# CAN_Expansion_V1.net
KiCad netlist of a schematic drawn in Altium Designer
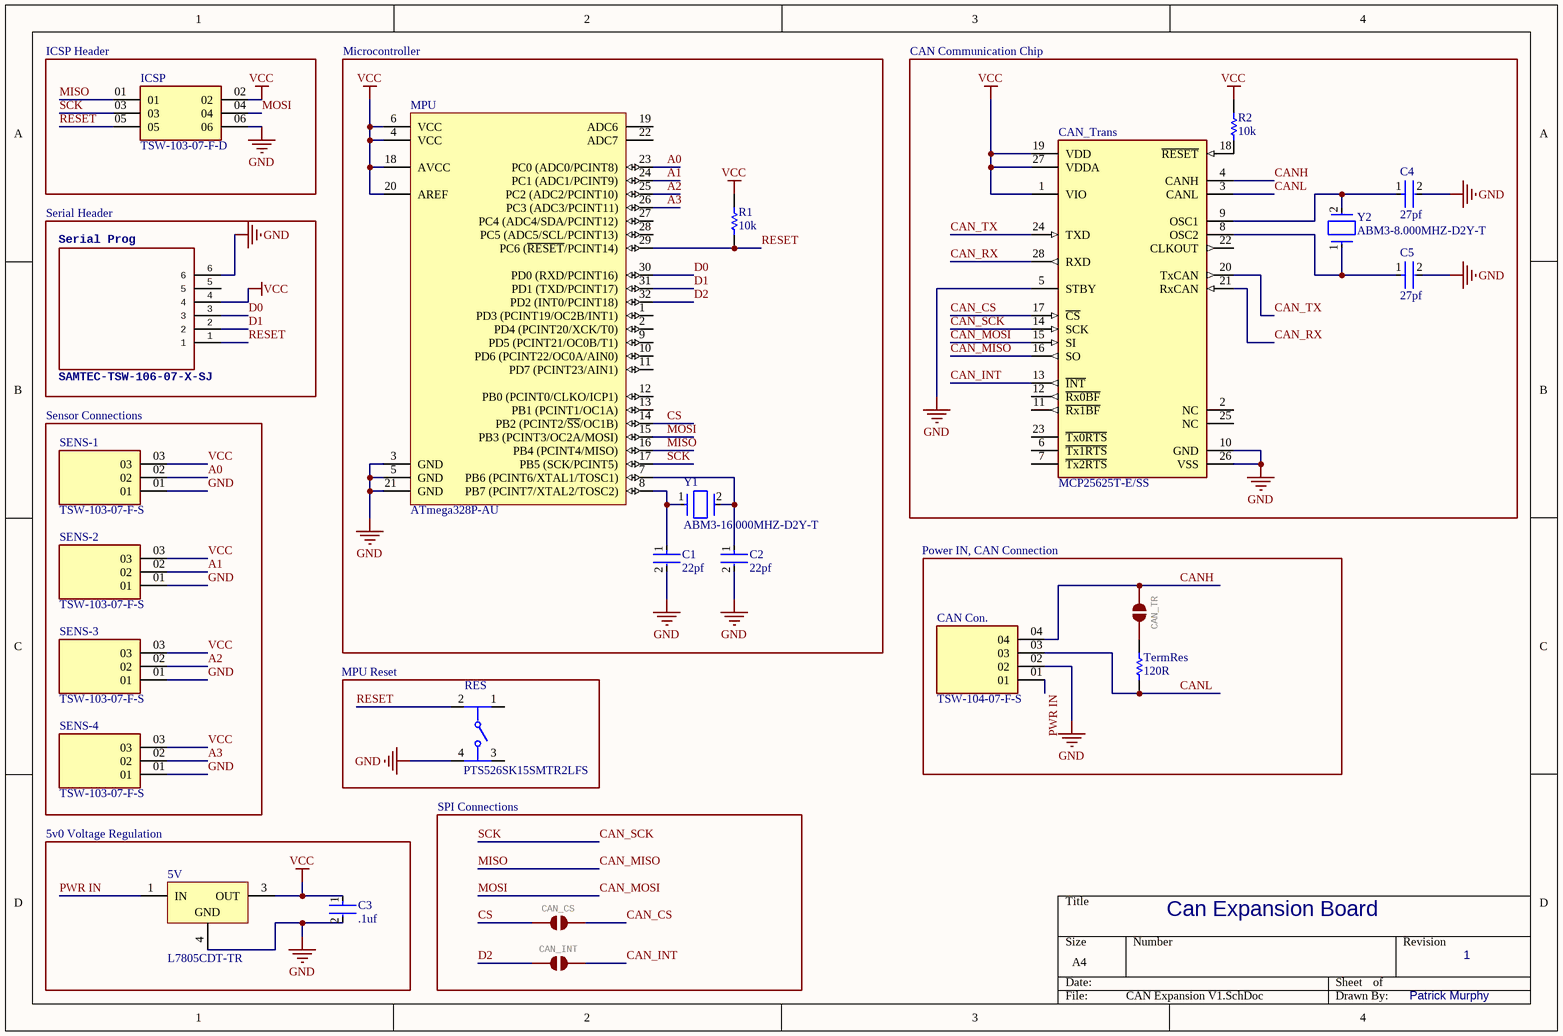
[diagram p0: CAN Expansion V1.SchDoc]

(export (version "E")
  (design (tool "Eeschema 10.0.6"))
  (components
    (comp (ref "5V")
      (value "L7805CDT-TR")
      (footprint "TO-252_N")
      (description "Positive Voltage Regulator, 3-Pin DPAK, Tape and Reel")
      (libsource (lib "Altium Content Vault") (part "PM-REG-L4940-SOT3"))
    )
    (comp (ref "C1")
      (value "22pf")
      (footprint "FP-GRM21B-0_15-IPC_C")
      (description "Chip Multilayer Ceramic Capacitors for General Purpose, 0805, 10uF, X5R, 15%, 10%, 25V")
      (fields (field (name "VOLTAGE") "25V") (field (name "TOLERANCE") "10%"))
      (libsource (lib "Altium Content Vault") (part "b4654b650e69147ec39a6b967a45e02"))
    )
    (comp (ref "C2")
      (value "22pf")
      (footprint "FP-GRM21B-0_15-IPC_C")
      (description "Chip Multilayer Ceramic Capacitors for General Purpose, 0805, 10uF, X5R, 15%, 10%, 25V")
      (fields (field (name "VOLTAGE") "25V") (field (name "TOLERANCE") "10%"))
      (libsource (lib "Altium Content Vault") (part "b4654b650e69147ec39a6b967a45e02"))
    )
    (comp (ref "C3")
      (value ".1uf")
      (footprint "FP-GRM21B-0_15-IPC_C")
      (description "Chip Multilayer Ceramic Capacitors for General Purpose, 0805, 10uF, X5R, 15%, 10%, 25V")
      (fields (field (name "VOLTAGE") "25V") (field (name "TOLERANCE") "10%"))
      (libsource (lib "Altium Content Vault") (part "b4654b650e69147ec39a6b967a45e02"))
    )
    (comp (ref "C4")
      (value "27pf")
      (footprint "FP-GRM21B-0_15-IPC_C")
      (description "Chip Multilayer Ceramic Capacitors for General Purpose, 0805, 10uF, X5R, 15%, 10%, 25V")
      (fields (field (name "VOLTAGE") "25V") (field (name "TOLERANCE") "10%"))
      (libsource (lib "Altium Content Vault") (part "b4654b650e69147ec39a6b967a45e02"))
    )
    (comp (ref "C5")
      (value "27pf")
      (footprint "FP-GRM21B-0_15-IPC_C")
      (description "Chip Multilayer Ceramic Capacitors for General Purpose, 0805, 10uF, X5R, 15%, 10%, 25V")
      (fields (field (name "VOLTAGE") "25V") (field (name "TOLERANCE") "10%"))
      (libsource (lib "Altium Content Vault") (part "b4654b650e69147ec39a6b967a45e02"))
    )
    (comp (ref "CAN Con.")
      (value "TSW-104-07-F-S")
      (footprint "SAMTEC_TSW-104-07-F-S")
      (fields (field (name "MF") "Samtec"))
      (libsource (lib "TSW-104-07-F-S") (part "TSW-104-07-F-S"))
    )
    (comp (ref "CAN_CS")
      (value "~")
      (footprint "SMT-JUMPER_2_NO_SILK")
      (libsource (lib "SparkFun-Jumpers.Library") (part "JUMPER-SMT_2_NO_SILK"))
    )
    (comp (ref "CAN_INT")
      (value "~")
      (footprint "SMT-JUMPER_2_NO_SILK")
      (libsource (lib "SparkFun-Jumpers.Library") (part "JUMPER-SMT_2_NO_SILK"))
    )
    (comp (ref "CAN_TR")
      (value "~")
      (footprint "SMT-JUMPER_2_NO_SILK")
      (libsource (lib "SparkFun-Jumpers.Library") (part "JUMPER-SMT_2_NO_SILK"))
    )
    (comp (ref "CAN_Trans")
      (value "MCP25625T-E/SS")
      (footprint "FP-C04-073-IPC_B")
      (description "IC TRANSCEIVER 1/1 28SSOP")
      (libsource (lib "Altium Content Vault") (part "1eb43db0d86e80dbea2ef2edec005e1"))
    )
    (comp (ref "ICSP")
      (value "TSW-103-07-F-D")
      (footprint "SAMTEC_TSW-103-07-F-D")
      (fields (field (name "MF") "Samtec"))
      (libsource (lib "TSW-103-07-F-D") (part "TSW-103-07-F-D"))
    )
    (comp (ref "MPU")
      (value "ATmega328P-AU")
      (footprint "32A_M")
      (libsource (lib "Altium Content Vault") (part "MC-8B-ATM48-SQ32"))
    )
    (comp (ref "R1")
      (value "10k")
      (footprint "RESC2013X60X40LL20T25")
      (fields (field (name "PART NUMBER") "ERA6AEB473V") (field (name "MANUFACTURER") "Panasonic"))
      (libsource (lib "Altium Content Vault") (part "RES"))
    )
    (comp (ref "R2")
      (value "10k")
      (footprint "RESC2013X60X40LL20T25")
      (fields (field (name "PART NUMBER") "ERA6AEB473V") (field (name "MANUFACTURER") "Panasonic"))
      (libsource (lib "Altium Content Vault") (part "RES"))
    )
    (comp (ref "RES")
      (value "PTS526SK15SMTR2LFS")
      (footprint "FP-PTS526SK15SMTR2LFS-MFG")
      (description "TACT 5.2 X 5.2, 1.5 MM H, 260GF,")
      (fields
        (field (name "MANUFACTURER") "C&K")
        (field (name "OCTOPART") "https://octopart.com/pts526+sk15+smtr2+lfs-c%26k+components-100617999")
      )
      (libsource (lib "Altium Content Vault") (part "b8895f3f4cefb76e1819d2863dba89b"))
    )
    (comp (ref "SENS-1")
      (value "TSW-103-07-F-S")
      (footprint "SAMTEC_TSW-103-07-F-S")
      (fields (field (name "MF") "Samtec"))
      (libsource (lib "TSW-103-07-F-S") (part "TSW-103-07-F-S"))
    )
    (comp (ref "SENS-2")
      (value "TSW-103-07-F-S")
      (footprint "SAMTEC_TSW-103-07-F-S")
      (fields (field (name "MF") "Samtec"))
      (libsource (lib "TSW-103-07-F-S") (part "TSW-103-07-F-S"))
    )
    (comp (ref "SENS-3")
      (value "TSW-103-07-F-S")
      (footprint "SAMTEC_TSW-103-07-F-S")
      (fields (field (name "MF") "Samtec"))
      (libsource (lib "TSW-103-07-F-S") (part "TSW-103-07-F-S"))
    )
    (comp (ref "SENS-4")
      (value "TSW-103-07-F-S")
      (footprint "SAMTEC_TSW-103-07-F-S")
      (fields (field (name "MF") "Samtec"))
      (libsource (lib "TSW-103-07-F-S") (part "TSW-103-07-F-S"))
    )
    (comp (ref "Serial Prog")
      (value "SAMTEC-TSW-106-07-X-SJ")
      (footprint "SAMTEC-TSW-106-07-X-S")
      (libsource (lib "TSW-106-07-F-S") (part "SAMTEC-TSW-106-07-X-SJ"))
    )
    (comp (ref "TermRes")
      (value "120R")
      (footprint "RESC2013X60X40LL20T25")
      (fields (field (name "PART NUMBER") "ERA6AEB473V") (field (name "MANUFACTURER") "Panasonic"))
      (libsource (lib "Altium Content Vault") (part "RES"))
    )
    (comp (ref "Y1")
      (value "ABM3-16.000MHZ-D2Y-T")
      (footprint "FP-ABM3-MFG")
      (description "Crystal 16MHz ±20ppm 18pF SMD-2 5mm x 3.2mm")
      (fields (field (name "TOLERANCE") "20ppm"))
      (libsource (lib "Altium Content Vault") (part "c23a69dc6c9e2f18f2079038eb95dd1"))
    )
    (comp (ref "Y2")
      (value "ABM3-8.000MHZ-D2Y-T")
      (footprint "FP-ABM3-MFG")
      (description "Crystal 8MHz ±20ppm 18pF SMD-2 5mm x 3.2mm")
      (fields (field (name "TOLERANCE") "20ppm"))
      (libsource (lib "Altium Content Vault") (part "c23a69dc6c9e2f18f2079038eb95dd1"))
    )
  )
  (nets
    (net (code "1") (name "/A0") (class "Default")
      (node (ref "MPU") (pin "23") (pinfunction "PC0_(ADC0/PCINT8)_23") (pintype "bidirectional"))
      (node (ref "SENS-1") (pin "02") (pinfunction "02_02") (pintype "passive"))
    )
    (net (code "2") (name "/A1") (class "Default")
      (node (ref "MPU") (pin "24") (pinfunction "PC1_(ADC1/PCINT9)_24") (pintype "bidirectional"))
      (node (ref "SENS-2") (pin "02") (pinfunction "02_02") (pintype "passive"))
    )
    (net (code "3") (name "/A2") (class "Default")
      (node (ref "MPU") (pin "25") (pinfunction "PC2_(ADC2/PCINT10)_25") (pintype "bidirectional"))
      (node (ref "SENS-3") (pin "02") (pinfunction "02_02") (pintype "passive"))
    )
    (net (code "4") (name "/A3") (class "Default")
      (node (ref "MPU") (pin "26") (pinfunction "PC3_(ADC3/PCINT11)_26") (pintype "bidirectional"))
      (node (ref "SENS-4") (pin "02") (pinfunction "02_02") (pintype "passive"))
    )
    (net (code "5") (name "/CANH") (class "Default")
      (node (ref "CAN Con.") (pin "04") (pinfunction "04_04") (pintype "passive"))
      (node (ref "CAN_TR") (pin "1") (pinfunction "1_1") (pintype "passive"))
      (node (ref "CAN_Trans") (pin "4") (pinfunction "CANH_4") (pintype "passive"))
    )
    (net (code "6") (name "/CANL") (class "Default")
      (node (ref "CAN Con.") (pin "03") (pinfunction "03_03") (pintype "passive"))
      (node (ref "CAN_Trans") (pin "3") (pinfunction "CANL_3") (pintype "passive"))
      (node (ref "TermRes") (pin "1") (pinfunction "1_1") (pintype "passive"))
    )
    (net (code "7") (name "/CAN_CS") (class "Default")
      (node (ref "CAN_CS") (pin "2") (pinfunction "2_2") (pintype "passive"))
      (node (ref "CAN_Trans") (pin "17") (pinfunction "~{CS}_17") (pintype "input"))
    )
    (net (code "8") (name "/CAN_INT") (class "Default")
      (node (ref "CAN_INT") (pin "2") (pinfunction "2_2") (pintype "passive"))
      (node (ref "CAN_Trans") (pin "13") (pinfunction "~{INT}_13") (pintype "output"))
    )
    (net (code "9") (name "/CAN_MISO") (class "Default")
      (node (ref "CAN_Trans") (pin "16") (pinfunction "SO_16") (pintype "output"))
      (node (ref "ICSP") (pin "01") (pinfunction "01_01") (pintype "passive"))
      (node (ref "MPU") (pin "16") (pinfunction "PB4_(PCINT4/MISO)_16") (pintype "bidirectional"))
    )
    (net (code "10") (name "/CAN_MOSI") (class "Default")
      (node (ref "CAN_Trans") (pin "15") (pinfunction "SI_15") (pintype "input"))
      (node (ref "ICSP") (pin "04") (pinfunction "04_04") (pintype "passive"))
      (node (ref "MPU") (pin "15") (pinfunction "PB3_(PCINT3/OC2A/MOSI)_15") (pintype "bidirectional"))
    )
    (net (code "11") (name "/CAN_RX") (class "Default")
      (node (ref "CAN_Trans") (pin "21") (pinfunction "RxCAN_21") (pintype "input"))
      (node (ref "CAN_Trans") (pin "28") (pinfunction "RXD_28") (pintype "output"))
    )
    (net (code "12") (name "/CAN_SCK") (class "Default")
      (node (ref "CAN_Trans") (pin "14") (pinfunction "SCK_14") (pintype "input"))
      (node (ref "ICSP") (pin "03") (pinfunction "03_03") (pintype "passive"))
      (node (ref "MPU") (pin "17") (pinfunction "PB5_(SCK/PCINT5)_17") (pintype "bidirectional"))
    )
    (net (code "13") (name "/CAN_TX") (class "Default")
      (node (ref "CAN_Trans") (pin "20") (pinfunction "TxCAN_20") (pintype "output"))
      (node (ref "CAN_Trans") (pin "24") (pinfunction "TXD_24") (pintype "input"))
    )
    (net (code "14") (name "/CS") (class "Default")
      (node (ref "CAN_CS") (pin "1") (pinfunction "1_1") (pintype "passive"))
      (node (ref "MPU") (pin "14") (pinfunction "PB2_(PCINT2/~{SS}/OC1B)_14") (pintype "bidirectional"))
    )
    (net (code "15") (name "/D0") (class "Default")
      (node (ref "MPU") (pin "30") (pinfunction "PD0_(RXD/PCINT16)_30") (pintype "bidirectional"))
      (node (ref "Serial Prog") (pin "3") (pinfunction "3_3") (pintype "passive"))
    )
    (net (code "16") (name "/D1") (class "Default")
      (node (ref "MPU") (pin "31") (pinfunction "PD1_(TXD/PCINT17)_31") (pintype "bidirectional"))
      (node (ref "Serial Prog") (pin "2") (pinfunction "2_2") (pintype "passive"))
    )
    (net (code "17") (name "/D2") (class "Default")
      (node (ref "CAN_INT") (pin "1") (pinfunction "1_1") (pintype "passive"))
      (node (ref "MPU") (pin "32") (pinfunction "PD2_(INT0/PCINT18)_32") (pintype "bidirectional"))
    )
    (net (code "18") (name "/PWR IN") (class "Default")
      (node (ref "5V") (pin "1") (pinfunction "IN_1") (pintype "power_in"))
      (node (ref "CAN Con.") (pin "01") (pinfunction "01_01") (pintype "passive"))
    )
    (net (code "19") (name "/RESET") (class "Default")
      (node (ref "ICSP") (pin "05") (pinfunction "05_05") (pintype "passive"))
      (node (ref "MPU") (pin "29") (pinfunction "PC6_(~{RESET}/PCINT14)_29") (pintype "bidirectional"))
      (node (ref "R1") (pin "1") (pinfunction "1_1") (pintype "passive"))
      (node (ref "RES") (pin "2") (pinfunction "2_2") (pintype "passive"))
      (node (ref "Serial Prog") (pin "1") (pinfunction "1_1") (pintype "passive"))
    )
    (net (code "20") (name "GND") (class "Default")
      (node (ref "5V") (pin "4") (pinfunction "GND_4") (pintype "power_in"))
      (node (ref "C1") (pin "2") (pinfunction "2_2") (pintype "passive"))
      (node (ref "C2") (pin "2") (pinfunction "2_2") (pintype "passive"))
      (node (ref "C3") (pin "2") (pinfunction "2_2") (pintype "passive"))
      (node (ref "C4") (pin "2") (pinfunction "2_2") (pintype "passive"))
      (node (ref "C5") (pin "2") (pinfunction "2_2") (pintype "passive"))
      (node (ref "CAN Con.") (pin "02") (pinfunction "02_02") (pintype "passive"))
      (node (ref "CAN_Trans") (pin "10") (pinfunction "GND_10") (pintype "power_in"))
      (node (ref "CAN_Trans") (pin "26") (pinfunction "VSS_26") (pintype "power_in"))
      (node (ref "CAN_Trans") (pin "5") (pinfunction "STBY_5") (pintype "passive"))
      (node (ref "ICSP") (pin "06") (pinfunction "06_06") (pintype "passive"))
      (node (ref "MPU") (pin "21") (pinfunction "GND_21") (pintype "power_in"))
      (node (ref "MPU") (pin "3") (pinfunction "GND_3") (pintype "power_in"))
      (node (ref "MPU") (pin "5") (pinfunction "GND_5") (pintype "power_in"))
      (node (ref "RES") (pin "4") (pinfunction "4_4") (pintype "passive"))
      (node (ref "SENS-1") (pin "01") (pinfunction "01_01") (pintype "passive"))
      (node (ref "SENS-2") (pin "01") (pinfunction "01_01") (pintype "passive"))
      (node (ref "SENS-3") (pin "01") (pinfunction "01_01") (pintype "passive"))
      (node (ref "SENS-4") (pin "01") (pinfunction "01_01") (pintype "passive"))
      (node (ref "Serial Prog") (pin "6") (pinfunction "6_6") (pintype "passive"))
    )
    (net (code "21") (name "Net-(CAN_TR-Pad2)") (class "Default")
      (node (ref "CAN_TR") (pin "2") (pinfunction "2_2") (pintype "passive"))
      (node (ref "TermRes") (pin "2") (pinfunction "2_2") (pintype "passive"))
    )
    (net (code "22") (name "Net-(CAN_Trans-OSC1)") (class "Default")
      (node (ref "C4") (pin "1") (pinfunction "1_1") (pintype "passive"))
      (node (ref "CAN_Trans") (pin "9") (pinfunction "OSC1_9") (pintype "passive"))
      (node (ref "Y2") (pin "2") (pinfunction "2_2") (pintype "passive"))
    )
    (net (code "23") (name "Net-(CAN_Trans-OSC2)") (class "Default")
      (node (ref "C5") (pin "1") (pinfunction "1_1") (pintype "passive"))
      (node (ref "CAN_Trans") (pin "8") (pinfunction "OSC2_8") (pintype "passive"))
      (node (ref "Y2") (pin "1") (pinfunction "1_1") (pintype "passive"))
    )
    (net (code "24") (name "Net-(CAN_Trans-~{RESET})") (class "Default")
      (node (ref "CAN_Trans") (pin "18") (pinfunction "~{RESET}_18") (pintype "input"))
      (node (ref "R2") (pin "1") (pinfunction "1_1") (pintype "passive"))
    )
    (net (code "25") (name "Net-(MPU-PB6_(PCINT6{slash}XTAL1{slash}TOSC1))") (class "Default")
      (node (ref "C2") (pin "1") (pinfunction "1_1") (pintype "passive"))
      (node (ref "MPU") (pin "7") (pinfunction "PB6_(PCINT6/XTAL1/TOSC1)_7") (pintype "bidirectional"))
      (node (ref "Y1") (pin "2") (pinfunction "2_2") (pintype "passive"))
    )
    (net (code "26") (name "Net-(MPU-PB7_(PCINT7{slash}XTAL2{slash}TOSC2))") (class "Default")
      (node (ref "C1") (pin "1") (pinfunction "1_1") (pintype "passive"))
      (node (ref "MPU") (pin "8") (pinfunction "PB7_(PCINT7/XTAL2/TOSC2)_8") (pintype "bidirectional"))
      (node (ref "Y1") (pin "1") (pinfunction "1_1") (pintype "passive"))
    )
    (net (code "27") (name "VCC") (class "Default")
      (node (ref "5V") (pin "3") (pinfunction "OUT_3") (pintype "power_in"))
      (node (ref "C3") (pin "1") (pinfunction "1_1") (pintype "passive"))
      (node (ref "CAN_Trans") (pin "1") (pinfunction "VIO_1") (pintype "power_in"))
      (node (ref "CAN_Trans") (pin "19") (pinfunction "VDD_19") (pintype "power_in"))
      (node (ref "CAN_Trans") (pin "27") (pinfunction "VDDA_27") (pintype "power_in"))
      (node (ref "ICSP") (pin "02") (pinfunction "02_02") (pintype "passive"))
      (node (ref "MPU") (pin "18") (pinfunction "AVCC_18") (pintype "power_in"))
      (node (ref "MPU") (pin "20") (pinfunction "AREF_20") (pintype "passive"))
      (node (ref "MPU") (pin "4") (pinfunction "VCC_4") (pintype "power_in"))
      (node (ref "MPU") (pin "6") (pinfunction "VCC_6") (pintype "power_in"))
      (node (ref "R1") (pin "2") (pinfunction "2_2") (pintype "passive"))
      (node (ref "R2") (pin "2") (pinfunction "2_2") (pintype "passive"))
      (node (ref "SENS-1") (pin "03") (pinfunction "03_03") (pintype "passive"))
      (node (ref "SENS-2") (pin "03") (pinfunction "03_03") (pintype "passive"))
      (node (ref "SENS-3") (pin "03") (pinfunction "03_03") (pintype "passive"))
      (node (ref "SENS-4") (pin "03") (pinfunction "03_03") (pintype "passive"))
      (node (ref "Serial Prog") (pin "4") (pinfunction "4_4") (pintype "passive"))
    )
    (net (code "28") (name "unconnected-(CAN_Trans-CLKOUT-Pad22)") (class "Default")
      (node (ref "CAN_Trans") (pin "22") (pinfunction "CLKOUT_22") (pintype "output"))
    )
    (net (code "29") (name "unconnected-(CAN_Trans-NC-Pad2)") (class "Default")
      (node (ref "CAN_Trans") (pin "2") (pinfunction "NC_2") (pintype "passive"))
    )
    (net (code "30") (name "unconnected-(CAN_Trans-NC-Pad25)") (class "Default")
      (node (ref "CAN_Trans") (pin "25") (pinfunction "NC_25") (pintype "passive"))
    )
    (net (code "31") (name "unconnected-(CAN_Trans-~{Rx0BF}-Pad12)") (class "Default")
      (node (ref "CAN_Trans") (pin "12") (pinfunction "~{Rx0BF}_12") (pintype "output"))
    )
    (net (code "32") (name "unconnected-(CAN_Trans-~{Rx1BF}-Pad11)") (class "Default")
      (node (ref "CAN_Trans") (pin "11") (pinfunction "~{Rx1BF}_11") (pintype "output"))
    )
    (net (code "33") (name "unconnected-(CAN_Trans-~{Tx0RTS}-Pad23)") (class "Default")
      (node (ref "CAN_Trans") (pin "23") (pinfunction "~{Tx0RTS}_23") (pintype "passive"))
    )
    (net (code "34") (name "unconnected-(CAN_Trans-~{Tx1RTS}-Pad6)") (class "Default")
      (node (ref "CAN_Trans") (pin "6") (pinfunction "~{Tx1RTS}_6") (pintype "passive"))
    )
    (net (code "35") (name "unconnected-(CAN_Trans-~{Tx2RTS}-Pad7)") (class "Default")
      (node (ref "CAN_Trans") (pin "7") (pinfunction "~{Tx2RTS}_7") (pintype "passive"))
    )
    (net (code "36") (name "unconnected-(MPU-ADC6-Pad19)") (class "Default")
      (node (ref "MPU") (pin "19") (pinfunction "ADC6_19") (pintype "passive"))
    )
    (net (code "37") (name "unconnected-(MPU-ADC7-Pad22)") (class "Default")
      (node (ref "MPU") (pin "22") (pinfunction "ADC7_22") (pintype "passive"))
    )
    (net (code "38") (name "unconnected-(MPU-PB0_(PCINT0{slash}CLKO{slash}ICP1)-Pad12)") (class "Default")
      (node (ref "MPU") (pin "12") (pinfunction "PB0_(PCINT0/CLKO/ICP1)_12") (pintype "bidirectional"))
    )
    (net (code "39") (name "unconnected-(MPU-PB1_(PCINT1{slash}OC1A)-Pad13)") (class "Default")
      (node (ref "MPU") (pin "13") (pinfunction "PB1_(PCINT1/OC1A)_13") (pintype "bidirectional"))
    )
    (net (code "40") (name "unconnected-(MPU-PC4_(ADC4{slash}SDA{slash}PCINT12)-Pad27)") (class "Default")
      (node (ref "MPU") (pin "27") (pinfunction "PC4_(ADC4/SDA/PCINT12)_27") (pintype "bidirectional"))
    )
    (net (code "41") (name "unconnected-(MPU-PC5_(ADC5{slash}SCL{slash}PCINT13)-Pad28)") (class "Default")
      (node (ref "MPU") (pin "28") (pinfunction "PC5_(ADC5/SCL/PCINT13)_28") (pintype "bidirectional"))
    )
    (net (code "42") (name "unconnected-(MPU-PD3_(PCINT19{slash}OC2B{slash}INT1)-Pad1)") (class "Default")
      (node (ref "MPU") (pin "1") (pinfunction "PD3_(PCINT19/OC2B/INT1)_1") (pintype "bidirectional"))
    )
    (net (code "43") (name "unconnected-(MPU-PD4_(PCINT20{slash}XCK{slash}T0)-Pad2)") (class "Default")
      (node (ref "MPU") (pin "2") (pinfunction "PD4_(PCINT20/XCK/T0)_2") (pintype "bidirectional"))
    )
    (net (code "44") (name "unconnected-(MPU-PD5_(PCINT21{slash}OC0B{slash}T1)-Pad9)") (class "Default")
      (node (ref "MPU") (pin "9") (pinfunction "PD5_(PCINT21/OC0B/T1)_9") (pintype "bidirectional"))
    )
    (net (code "45") (name "unconnected-(MPU-PD6_(PCINT22{slash}OC0A{slash}AIN0)-Pad10)") (class "Default")
      (node (ref "MPU") (pin "10") (pinfunction "PD6_(PCINT22/OC0A/AIN0)_10") (pintype "bidirectional"))
    )
    (net (code "46") (name "unconnected-(MPU-PD7_(PCINT23{slash}AIN1)-Pad11)") (class "Default")
      (node (ref "MPU") (pin "11") (pinfunction "PD7_(PCINT23/AIN1)_11") (pintype "bidirectional"))
    )
    (net (code "47") (name "unconnected-(RES-Pad1)") (class "Default")
      (node (ref "RES") (pin "1") (pinfunction "1_1") (pintype "passive"))
    )
    (net (code "48") (name "unconnected-(RES-Pad3)") (class "Default")
      (node (ref "RES") (pin "3") (pinfunction "3_3") (pintype "passive"))
    )
    (net (code "49") (name "unconnected-(Serial Prog-Pad5)") (class "Default")
      (node (ref "Serial Prog") (pin "5") (pinfunction "5_5") (pintype "passive"))
    )
  )
)
